# PAGE4_-_SENSORS_ALEKSEJ_nov_-02-112449-2.net
KiCad netlist of a schematic drawn in Altium Designer
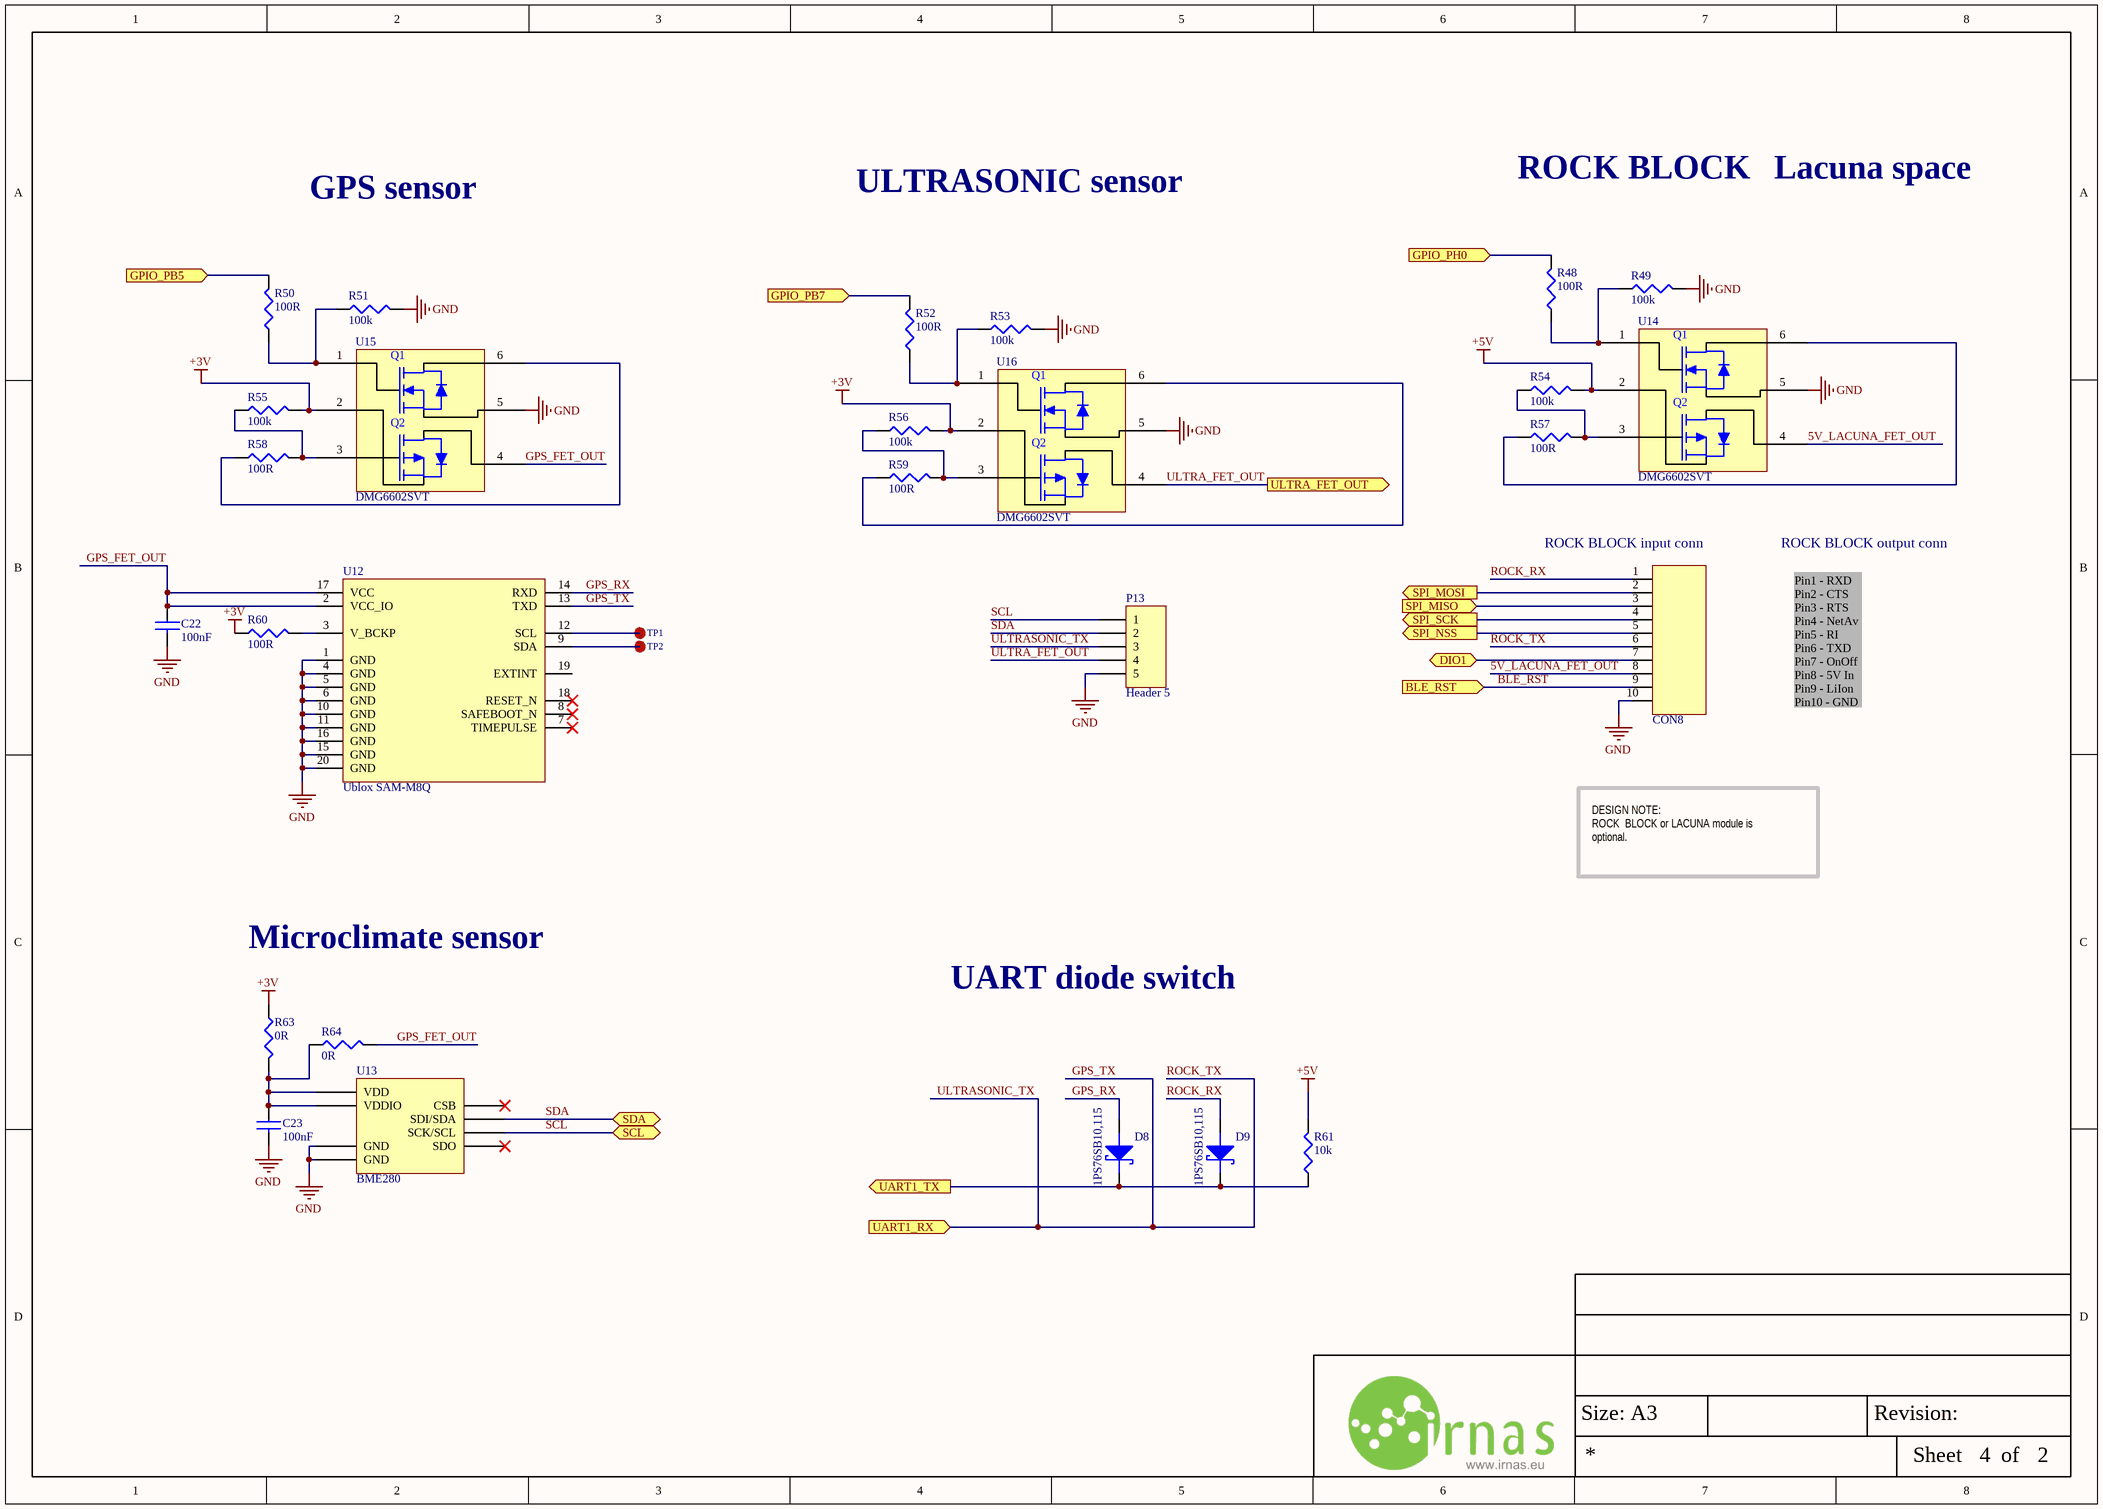
[diagram p0: PAGE4 - SENSORS_ALEKSEJ_nov.-02-112449-2020_Conflict.SchDoc]

(export (version "E")
  (design (tool "Eeschema 10.0.6"))
  (components
    (comp (ref "C22")
      (value "100nF")
      (footprint "CAP0603")
      (description "MURATA - GRM188R71C104KA01J - CAP, MLCC, X7R, 0.1UF, 16V, 0603")
      (fields
        (field (name "MANUFACTURER") "MURATA")
        (field (name "MANUFACTURER PART NUMBER") "GRM188R71C104KA01J")
      )
      (libsource (lib "Passive") (part "C - 100nF"))
    )
    (comp (ref "C23")
      (value "100nF")
      (footprint "CAP0603")
      (description "MURATA - GRM188R71C104KA01J - CAP, MLCC, X7R, 0.1UF, 16V, 0603")
      (fields
        (field (name "MANUFACTURER") "MURATA")
        (field (name "MANUFACTURER PART NUMBER") "GRM188R71C104KA01J")
      )
      (libsource (lib "Passive") (part "C - 100nF"))
    )
    (comp (ref "CON8")
      (value "53261-1071")
      (footprint "PICOBLADE 10PIN")
      (description "Wire-To-Board Connector, Right Angle, 1.25 mm, 10 Contacts, Header, PicoBlade 53261 Series")
      (libsource (lib "Connectors") (part "PicoBlade 10pin"))
    )
    (comp (ref "D8")
      (value "1PS76SB10,115")
      (footprint "SOD-323")
      (description "Small Signal Schottky Diode, Single, 30 V, 200 mA, 320 mV, 800 mA, 125 °C")
      (libsource (lib "Active") (part "DS - 1PS76SB10,115"))
    )
    (comp (ref "D9")
      (value "1PS76SB10,115")
      (footprint "SOD-323")
      (description "Small Signal Schottky Diode, Single, 30 V, 200 mA, 320 mV, 800 mA, 125 °C")
      (libsource (lib "Active") (part "DS - 1PS76SB10,115"))
    )
    (comp (ref "P13")
      (value "Header 5")
      (footprint "HDR1X5")
      (description "Header, 5-Pin")
      (fields (field (name "PUBLISHER") "Altium Limited"))
      (libsource (lib "Miscellaneous Connectors") (part "Header 5"))
    )
    (comp (ref "R48")
      (value "100R")
      (footprint "RES0603")
      (description "MULTICOMP - MC0063W06031100R - RES, THICK FILM, 100R, 1%, 0.063W, 0603")
      (fields
        (field (name "MANUFACTURER") "MULTICOMP")
        (field (name "MANUFACTURER PART NUMBER") "MC0063W06031100R")
      )
      (libsource (lib "Passive") (part "R - 100R"))
    )
    (comp (ref "R49")
      (value "100k")
      (footprint "RES0603")
      (description "MULTICOMP - MCMR06X104 JTL - RES, CERAMIC, 100K, 5%, 0.1W, 0603")
      (fields
        (field (name "MANUFACTURER") "MULTICOMP")
        (field (name "MANUFACTURER PART NUMBER") "MCMR06X104 JTL")
      )
      (libsource (lib "Passive") (part "R - 100k"))
    )
    (comp (ref "R50")
      (value "100R")
      (footprint "RES0603")
      (description "MULTICOMP - MC0063W06031100R - RES, THICK FILM, 100R, 1%, 0.063W, 0603")
      (fields
        (field (name "MANUFACTURER") "MULTICOMP")
        (field (name "MANUFACTURER PART NUMBER") "MC0063W06031100R")
      )
      (libsource (lib "Passive") (part "R - 100R"))
    )
    (comp (ref "R51")
      (value "100k")
      (footprint "RES0603")
      (description "MULTICOMP - MCMR06X104 JTL - RES, CERAMIC, 100K, 5%, 0.1W, 0603")
      (fields
        (field (name "MANUFACTURER") "MULTICOMP")
        (field (name "MANUFACTURER PART NUMBER") "MCMR06X104 JTL")
      )
      (libsource (lib "Passive") (part "R - 100k"))
    )
    (comp (ref "R52")
      (value "100R")
      (footprint "RES0603")
      (description "MULTICOMP - MC0063W06031100R - RES, THICK FILM, 100R, 1%, 0.063W, 0603")
      (fields
        (field (name "MANUFACTURER") "MULTICOMP")
        (field (name "MANUFACTURER PART NUMBER") "MC0063W06031100R")
      )
      (libsource (lib "Passive") (part "R - 100R"))
    )
    (comp (ref "R53")
      (value "100k")
      (footprint "RES0603")
      (description "MULTICOMP - MCMR06X104 JTL - RES, CERAMIC, 100K, 5%, 0.1W, 0603")
      (fields
        (field (name "MANUFACTURER") "MULTICOMP")
        (field (name "MANUFACTURER PART NUMBER") "MCMR06X104 JTL")
      )
      (libsource (lib "Passive") (part "R - 100k"))
    )
    (comp (ref "R54")
      (value "100k")
      (footprint "RES0603")
      (description "MULTICOMP - MCMR06X104 JTL - RES, CERAMIC, 100K, 5%, 0.1W, 0603")
      (fields
        (field (name "MANUFACTURER") "MULTICOMP")
        (field (name "MANUFACTURER PART NUMBER") "MCMR06X104 JTL")
      )
      (libsource (lib "Passive") (part "R - 100k"))
    )
    (comp (ref "R55")
      (value "100k")
      (footprint "RES0603")
      (description "MULTICOMP - MCMR06X104 JTL - RES, CERAMIC, 100K, 5%, 0.1W, 0603")
      (fields
        (field (name "MANUFACTURER") "MULTICOMP")
        (field (name "MANUFACTURER PART NUMBER") "MCMR06X104 JTL")
      )
      (libsource (lib "Passive") (part "R - 100k"))
    )
    (comp (ref "R56")
      (value "100k")
      (footprint "RES0603")
      (description "MULTICOMP - MCMR06X104 JTL - RES, CERAMIC, 100K, 5%, 0.1W, 0603")
      (fields
        (field (name "MANUFACTURER") "MULTICOMP")
        (field (name "MANUFACTURER PART NUMBER") "MCMR06X104 JTL")
      )
      (libsource (lib "Passive") (part "R - 100k"))
    )
    (comp (ref "R57")
      (value "100R")
      (footprint "RES0603")
      (description "MULTICOMP - MC0063W06031100R - RES, THICK FILM, 100R, 1%, 0.063W, 0603")
      (fields
        (field (name "MANUFACTURER") "MULTICOMP")
        (field (name "MANUFACTURER PART NUMBER") "MC0063W06031100R")
      )
      (libsource (lib "Passive") (part "R - 100R"))
    )
    (comp (ref "R58")
      (value "100R")
      (footprint "RES0603")
      (description "MULTICOMP - MC0063W06031100R - RES, THICK FILM, 100R, 1%, 0.063W, 0603")
      (fields
        (field (name "MANUFACTURER") "MULTICOMP")
        (field (name "MANUFACTURER PART NUMBER") "MC0063W06031100R")
      )
      (libsource (lib "Passive") (part "R - 100R"))
    )
    (comp (ref "R59")
      (value "100R")
      (footprint "RES0603")
      (description "MULTICOMP - MC0063W06031100R - RES, THICK FILM, 100R, 1%, 0.063W, 0603")
      (fields
        (field (name "MANUFACTURER") "MULTICOMP")
        (field (name "MANUFACTURER PART NUMBER") "MC0063W06031100R")
      )
      (libsource (lib "Passive") (part "R - 100R"))
    )
    (comp (ref "R60")
      (value "100R")
      (footprint "RES0603")
      (description "MULTICOMP - MC0063W06031100R - RES, THICK FILM, 100R, 1%, 0.063W, 0603")
      (fields
        (field (name "MANUFACTURER") "MULTICOMP")
        (field (name "MANUFACTURER PART NUMBER") "MC0063W06031100R")
      )
      (libsource (lib "Passive") (part "R - 100R"))
    )
    (comp (ref "R61")
      (value "10k")
      (footprint "RES0603")
      (description "MULTICOMP - MCMR06X103 JTL - RES, CERAMIC, 10K, 5%, 0.1W, 0603")
      (fields
        (field (name "MANUFACTURER") "MULTICOMP")
        (field (name "MANUFACTURER PART NUMBER") "MCMR06X103 JTL")
      )
      (libsource (lib "Passive") (part "R - 10k"))
    )
    (comp (ref "R63")
      (value "0R")
      (footprint "RES0603")
      (description "BOURNS - CR0603-J/-000ELF - RES, THICK FILM, 0R, 5%, 0.1W, 0603")
      (fields
        (field (name "MANUFACTURER") "BOURNS")
        (field (name "MANUFACTURER PART NUMBER") "CR0603-J/-000ELF")
      )
      (libsource (lib "Passive") (part "R - 0R"))
    )
    (comp (ref "R64")
      (value "0R")
      (footprint "RES0603")
      (description "BOURNS - CR0603-J/-000ELF - RES, THICK FILM, 0R, 5%, 0.1W, 0603")
      (fields
        (field (name "MANUFACTURER") "BOURNS")
        (field (name "MANUFACTURER PART NUMBER") "CR0603-J/-000ELF")
      )
      (libsource (lib "Passive") (part "R - 0R"))
    )
    (comp (ref "TP1")
      (value "TestPoint")
      (footprint "Passive:TestPoint:1.2x1.2mm")
      (description "TEST POINT ROUND SMD")
      (libsource (lib "Passive") (part "TestPoint"))
    )
    (comp (ref "TP2")
      (value "TestPoint")
      (footprint "Passive:TestPoint:1.2x1.2mm")
      (description "TEST POINT ROUND SMD")
      (libsource (lib "Passive") (part "TestPoint"))
    )
    (comp (ref "U12")
      (value "Ublox SAM-M8Q")
      (footprint "SAM-M8Q")
      (description "SAM-M8 RF Receiver BeiDou, Galileo, GLONASS, GNSS, GPS -160dBm")
      (fields (field (name "MANUFACTURER") "u-blox") (field (name "MANUFACTURER PART NUMBER") "MAX-M8Q-0"))
      (libsource (lib "Active") (part "RF - UBLOX-SAM-M8Q"))
    )
    (comp (ref "U13")
      (value "BME280")
      (footprint "BME280")
      (description "Humidity Temperature Sensor 0 ~ 100% RH I²C, SPI ±3% 1s Surface Mount")
      (libsource (lib "Active") (part "SEN - BME280"))
    )
    (comp (ref "U14")
      (value "DMG6602SVT")
      (footprint "TSOT26")
      (description "Dual MOSFET, N and P Channel, 3.4 A, 30 V, 0.038 ohm, 10 V, 1 V")
      (libsource (lib "Active") (part "T_M - DMG6602SVT"))
    )
    (comp (ref "U15")
      (value "DMG6602SVT")
      (footprint "TSOT26")
      (description "Dual MOSFET, N and P Channel, 3.4 A, 30 V, 0.038 ohm, 10 V, 1 V")
      (libsource (lib "Active") (part "T_M - DMG6602SVT"))
    )
    (comp (ref "U16")
      (value "DMG6602SVT")
      (footprint "TSOT26")
      (description "Dual MOSFET, N and P Channel, 3.4 A, 30 V, 0.038 ohm, 10 V, 1 V")
      (libsource (lib "Active") (part "T_M - DMG6602SVT"))
    )
  )
  (nets
    (net (code "1") (name "+3V") (class "Default")
      (node (ref "R55") (pin "2") (pinfunction "2_2") (pintype "passive"))
      (node (ref "R56") (pin "2") (pinfunction "2_2") (pintype "passive"))
      (node (ref "R60") (pin "1") (pinfunction "1_1") (pintype "passive"))
      (node (ref "R63") (pin "1") (pinfunction "1_1") (pintype "passive"))
      (node (ref "U15") (pin "2") (pinfunction "S2_2") (pintype "open_collector"))
      (node (ref "U16") (pin "2") (pinfunction "S2_2") (pintype "open_collector"))
    )
    (net (code "2") (name "+5V") (class "Default")
      (node (ref "R54") (pin "2") (pinfunction "2_2") (pintype "passive"))
      (node (ref "R61") (pin "2") (pinfunction "2_2") (pintype "passive"))
      (node (ref "U14") (pin "2") (pinfunction "S2_2") (pintype "open_collector"))
    )
    (net (code "3") (name "/5V_LACUNA_FET_OUT") (class "Default")
      (node (ref "CON8") (pin "8") (pinfunction "8_8") (pintype "passive"))
      (node (ref "U14") (pin "4") (pinfunction "D2_4") (pintype "open_collector"))
    )
    (net (code "4") (name "/BLE_RST") (class "Default")
      (node (ref "CON8") (pin "9") (pinfunction "9_9") (pintype "passive"))
    )
    (net (code "5") (name "/DIO1") (class "Default")
      (node (ref "CON8") (pin "7") (pinfunction "7_7") (pintype "passive"))
    )
    (net (code "6") (name "/GPIO_PB5") (class "Default")
      (node (ref "R50") (pin "2") (pinfunction "2_2") (pintype "passive"))
    )
    (net (code "7") (name "/GPIO_PB7") (class "Default")
      (node (ref "R52") (pin "2") (pinfunction "2_2") (pintype "passive"))
    )
    (net (code "8") (name "/GPIO_PH0") (class "Default")
      (node (ref "R48") (pin "2") (pinfunction "2_2") (pintype "passive"))
    )
    (net (code "9") (name "/GPS_FET_OUT") (class "Default")
      (node (ref "C22") (pin "1") (pinfunction "1_1") (pintype "passive"))
      (node (ref "R64") (pin "2") (pinfunction "2_2") (pintype "passive"))
      (node (ref "U12") (pin "17") (pinfunction "VCC_17") (pintype "passive"))
      (node (ref "U12") (pin "2") (pinfunction "VCC_IO_2") (pintype "passive"))
      (node (ref "U15") (pin "4") (pinfunction "D2_4") (pintype "open_collector"))
    )
    (net (code "10") (name "/GPS_RX") (class "Default")
      (node (ref "D8") (pin "2") (pinfunction "ANODE_2") (pintype "passive"))
      (node (ref "U12") (pin "14") (pinfunction "RXD_14") (pintype "passive"))
    )
    (net (code "11") (name "/GPS_TX") (class "Default")
      (node (ref "CON8") (pin "6") (pinfunction "6_6") (pintype "passive"))
      (node (ref "P13") (pin "3") (pinfunction "3_3") (pintype "passive"))
      (node (ref "U12") (pin "13") (pinfunction "TXD_13") (pintype "passive"))
    )
    (net (code "12") (name "/ROCK_RX") (class "Default")
      (node (ref "CON8") (pin "1") (pinfunction "1_1") (pintype "passive"))
      (node (ref "D9") (pin "2") (pinfunction "ANODE_2") (pintype "passive"))
    )
    (net (code "13") (name "/SCL") (class "Default")
      (node (ref "P13") (pin "1") (pinfunction "1_1") (pintype "passive"))
      (node (ref "U13") (pin "4") (pinfunction "SCK/SCL_4") (pintype "passive"))
    )
    (net (code "14") (name "/SDA") (class "Default")
      (node (ref "P13") (pin "2") (pinfunction "2_2") (pintype "passive"))
      (node (ref "U13") (pin "3") (pinfunction "SDI/SDA_3") (pintype "passive"))
    )
    (net (code "15") (name "/SPI_MISO") (class "Default")
      (node (ref "CON8") (pin "3") (pinfunction "3_3") (pintype "passive"))
    )
    (net (code "16") (name "/SPI_MOSI") (class "Default")
      (node (ref "CON8") (pin "2") (pinfunction "2_2") (pintype "passive"))
    )
    (net (code "17") (name "/SPI_NSS") (class "Default")
      (node (ref "CON8") (pin "5") (pinfunction "5_5") (pintype "passive"))
    )
    (net (code "18") (name "/SPI_SCK") (class "Default")
      (node (ref "CON8") (pin "4") (pinfunction "4_4") (pintype "passive"))
    )
    (net (code "19") (name "/UART1_TX") (class "Default")
      (node (ref "D8") (pin "1") (pinfunction "cathode_1") (pintype "passive"))
      (node (ref "D9") (pin "1") (pinfunction "cathode_1") (pintype "passive"))
      (node (ref "R61") (pin "1") (pinfunction "1_1") (pintype "passive"))
    )
    (net (code "20") (name "/ULTRA_FET_OUT") (class "Default")
      (node (ref "P13") (pin "4") (pinfunction "4_4") (pintype "passive"))
      (node (ref "U16") (pin "4") (pinfunction "D2_4") (pintype "open_collector"))
    )
    (net (code "21") (name "GND") (class "Default")
      (node (ref "C22") (pin "2") (pinfunction "2_2") (pintype "passive"))
      (node (ref "C23") (pin "2") (pinfunction "2_2") (pintype "passive"))
      (node (ref "CON8") (pin "10") (pinfunction "10_10") (pintype "passive"))
      (node (ref "P13") (pin "5") (pinfunction "5_5") (pintype "passive"))
      (node (ref "R49") (pin "2") (pinfunction "2_2") (pintype "passive"))
      (node (ref "R51") (pin "2") (pinfunction "2_2") (pintype "passive"))
      (node (ref "R53") (pin "2") (pinfunction "2_2") (pintype "passive"))
      (node (ref "U12") (pin "1") (pinfunction "GND_1") (pintype "passive"))
      (node (ref "U12") (pin "10") (pinfunction "GND_10") (pintype "passive"))
      (node (ref "U12") (pin "11") (pinfunction "GND_11") (pintype "passive"))
      (node (ref "U12") (pin "15") (pinfunction "GND_15") (pintype "passive"))
      (node (ref "U12") (pin "16") (pinfunction "GND_16") (pintype "passive"))
      (node (ref "U12") (pin "20") (pinfunction "GND_20") (pintype "passive"))
      (node (ref "U12") (pin "4") (pinfunction "GND_4") (pintype "passive"))
      (node (ref "U12") (pin "5") (pinfunction "GND_5") (pintype "passive"))
      (node (ref "U12") (pin "6") (pinfunction "GND_6") (pintype "passive"))
      (node (ref "U13") (pin "1") (pinfunction "GND_1") (pintype "passive"))
      (node (ref "U13") (pin "7") (pinfunction "GND_7") (pintype "passive"))
      (node (ref "U14") (pin "5") (pinfunction "S1_5") (pintype "open_collector"))
      (node (ref "U15") (pin "5") (pinfunction "S1_5") (pintype "open_collector"))
      (node (ref "U16") (pin "5") (pinfunction "S1_5") (pintype "open_collector"))
    )
    (net (code "22") (name "Net-(U12-SCL)") (class "Default")
      (node (ref "TP1") (pin "0") (pinfunction "0_0") (pintype "passive"))
      (node (ref "U12") (pin "12") (pinfunction "SCL_12") (pintype "passive"))
    )
    (net (code "23") (name "Net-(U12-SDA)") (class "Default")
      (node (ref "TP2") (pin "0") (pinfunction "0_0") (pintype "passive"))
      (node (ref "U12") (pin "9") (pinfunction "SDA_9") (pintype "passive"))
    )
    (net (code "24") (name "Net-(U12-V_BCKP)") (class "Default")
      (node (ref "R60") (pin "2") (pinfunction "2_2") (pintype "passive"))
      (node (ref "U12") (pin "3") (pinfunction "V_BCKP_3") (pintype "passive"))
    )
    (net (code "25") (name "Net-(U13-VDD)") (class "Default")
      (node (ref "C23") (pin "1") (pinfunction "1_1") (pintype "passive"))
      (node (ref "R63") (pin "2") (pinfunction "2_2") (pintype "passive"))
      (node (ref "R64") (pin "1") (pinfunction "1_1") (pintype "passive"))
      (node (ref "U13") (pin "6") (pinfunction "VDDIO_6") (pintype "passive"))
      (node (ref "U13") (pin "8") (pinfunction "VDD_8") (pintype "passive"))
    )
    (net (code "26") (name "Net-(U14-D1)") (class "Default")
      (node (ref "R57") (pin "1") (pinfunction "1_1") (pintype "passive"))
      (node (ref "U14") (pin "6") (pinfunction "D1_6") (pintype "open_collector"))
    )
    (net (code "27") (name "Net-(U14-G1)") (class "Default")
      (node (ref "R48") (pin "1") (pinfunction "1_1") (pintype "passive"))
      (node (ref "R49") (pin "1") (pinfunction "1_1") (pintype "passive"))
      (node (ref "U14") (pin "1") (pinfunction "G1_1") (pintype "open_collector"))
    )
    (net (code "28") (name "Net-(U14-G2)") (class "Default")
      (node (ref "R54") (pin "1") (pinfunction "1_1") (pintype "passive"))
      (node (ref "R57") (pin "2") (pinfunction "2_2") (pintype "passive"))
      (node (ref "U14") (pin "3") (pinfunction "G2_3") (pintype "open_collector"))
    )
    (net (code "29") (name "Net-(U15-D1)") (class "Default")
      (node (ref "R58") (pin "1") (pinfunction "1_1") (pintype "passive"))
      (node (ref "U15") (pin "6") (pinfunction "D1_6") (pintype "open_collector"))
    )
    (net (code "30") (name "Net-(U15-G1)") (class "Default")
      (node (ref "R50") (pin "1") (pinfunction "1_1") (pintype "passive"))
      (node (ref "R51") (pin "1") (pinfunction "1_1") (pintype "passive"))
      (node (ref "U15") (pin "1") (pinfunction "G1_1") (pintype "open_collector"))
    )
    (net (code "31") (name "Net-(U15-G2)") (class "Default")
      (node (ref "R55") (pin "1") (pinfunction "1_1") (pintype "passive"))
      (node (ref "R58") (pin "2") (pinfunction "2_2") (pintype "passive"))
      (node (ref "U15") (pin "3") (pinfunction "G2_3") (pintype "open_collector"))
    )
    (net (code "32") (name "Net-(U16-D1)") (class "Default")
      (node (ref "R59") (pin "1") (pinfunction "1_1") (pintype "passive"))
      (node (ref "U16") (pin "6") (pinfunction "D1_6") (pintype "open_collector"))
    )
    (net (code "33") (name "Net-(U16-G1)") (class "Default")
      (node (ref "R52") (pin "1") (pinfunction "1_1") (pintype "passive"))
      (node (ref "R53") (pin "1") (pinfunction "1_1") (pintype "passive"))
      (node (ref "U16") (pin "1") (pinfunction "G1_1") (pintype "open_collector"))
    )
    (net (code "34") (name "Net-(U16-G2)") (class "Default")
      (node (ref "R56") (pin "1") (pinfunction "1_1") (pintype "passive"))
      (node (ref "R59") (pin "2") (pinfunction "2_2") (pintype "passive"))
      (node (ref "U16") (pin "3") (pinfunction "G2_3") (pintype "open_collector"))
    )
    (net (code "35") (name "unconnected-(U12-EXTINT-Pad19)") (class "Default")
      (node (ref "U12") (pin "19") (pinfunction "EXTINT_19") (pintype "passive"))
    )
    (net (code "36") (name "unconnected-(U12-RESET_N-Pad18)") (class "Default")
      (node (ref "U12") (pin "18") (pinfunction "RESET_N_18") (pintype "passive+no_connect"))
    )
    (net (code "37") (name "unconnected-(U12-SAFEBOOT_N-Pad8)") (class "Default")
      (node (ref "U12") (pin "8") (pinfunction "SAFEBOOT_N_8") (pintype "passive+no_connect"))
    )
    (net (code "38") (name "unconnected-(U12-TIMEPULSE-Pad7)") (class "Default")
      (node (ref "U12") (pin "7") (pinfunction "TIMEPULSE_7") (pintype "passive+no_connect"))
    )
    (net (code "39") (name "unconnected-(U13-CSB-Pad2)") (class "Default")
      (node (ref "U13") (pin "2") (pinfunction "CSB_2") (pintype "passive+no_connect"))
    )
    (net (code "40") (name "unconnected-(U13-SDO-Pad5)") (class "Default")
      (node (ref "U13") (pin "5") (pinfunction "SDO_5") (pintype "passive+no_connect"))
    )
  )
)
